# Power.net
KiCad netlist of a schematic drawn in Altium Designer
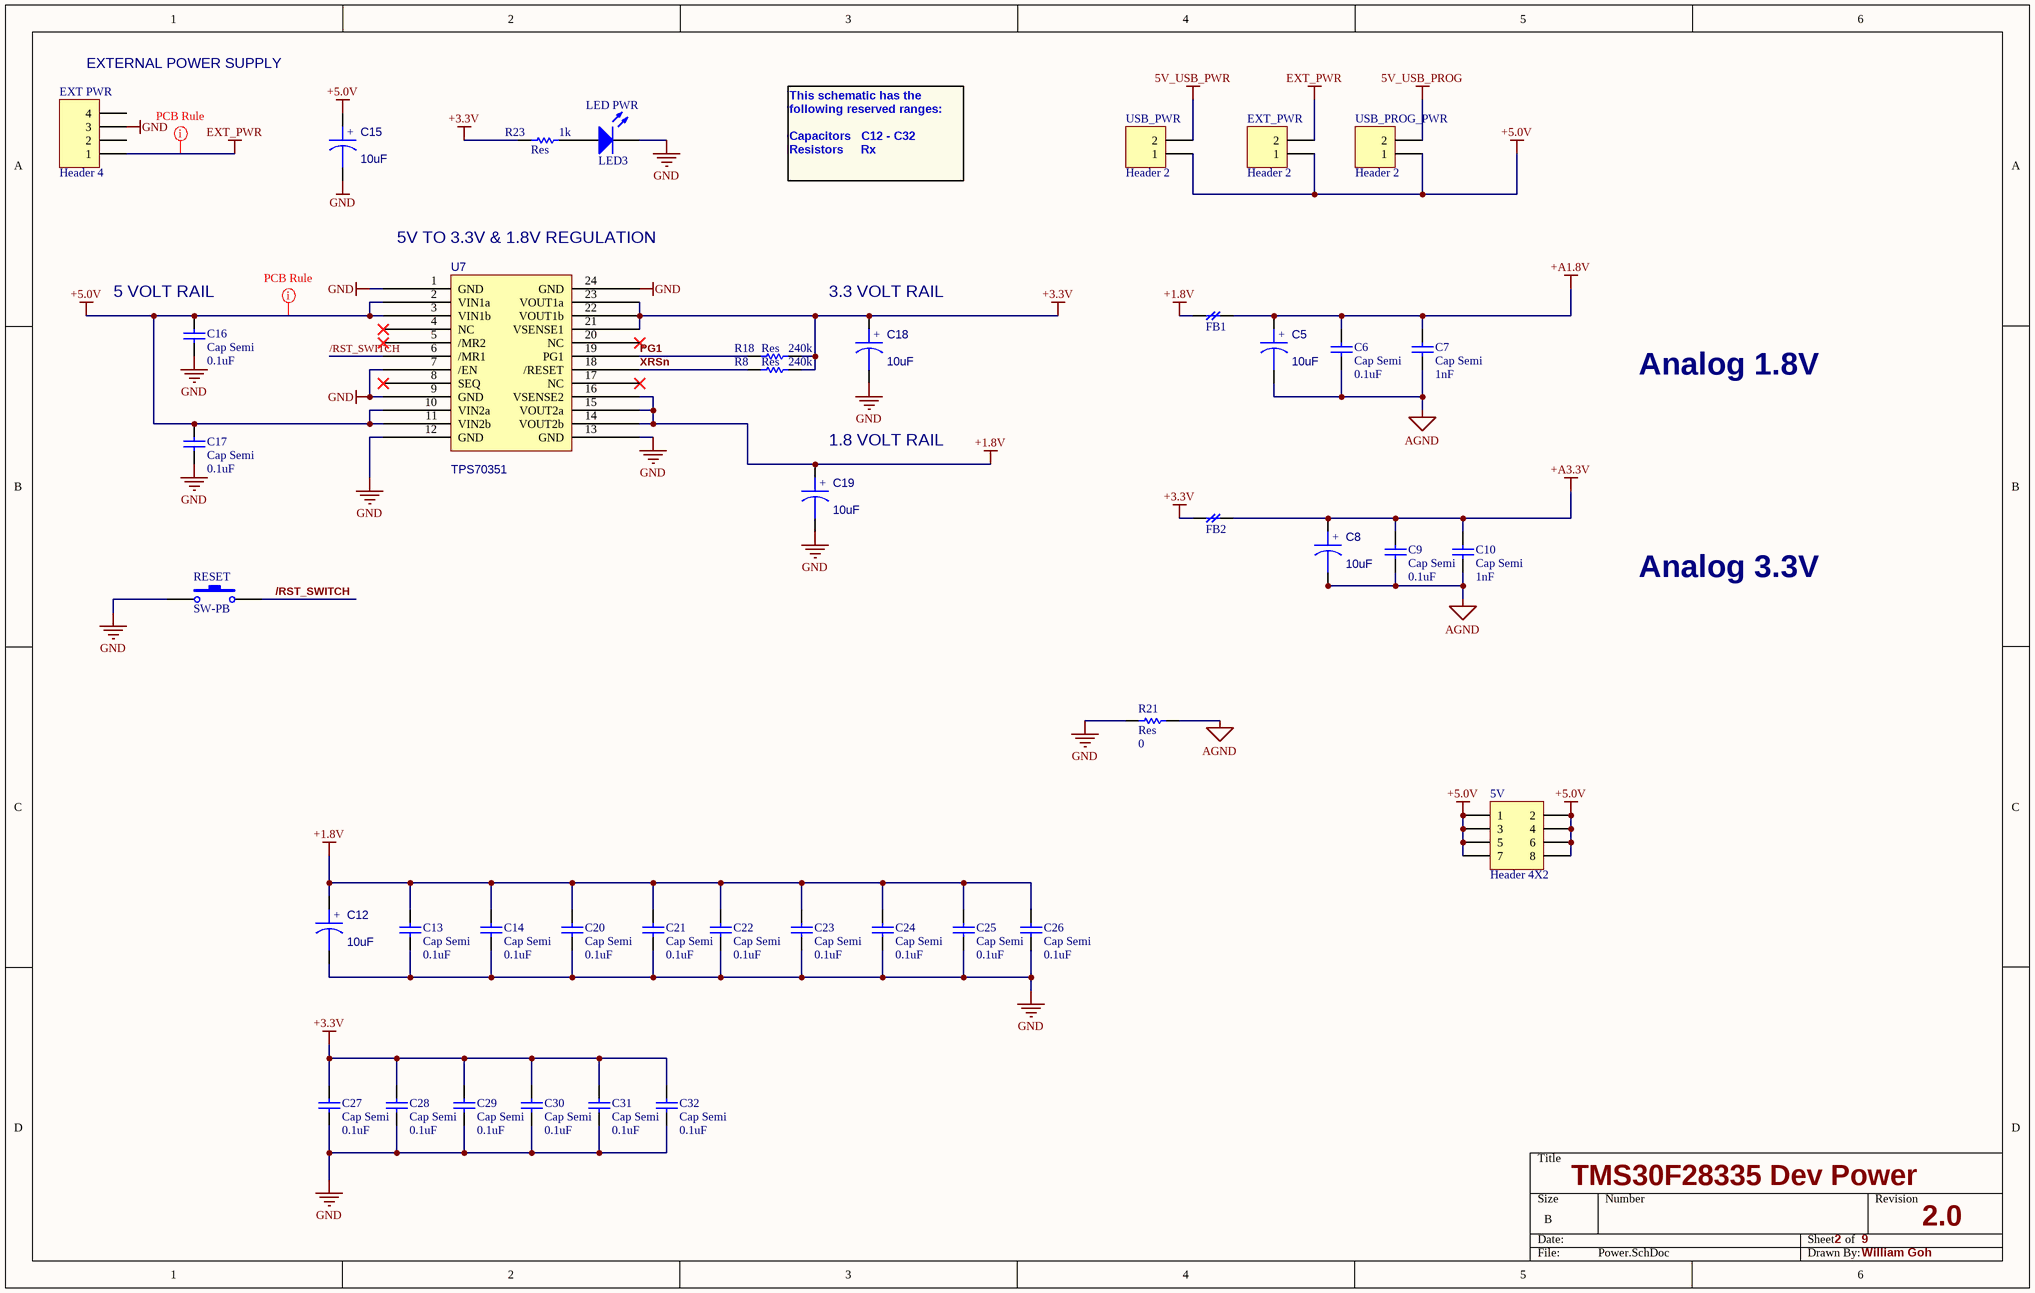
[diagram p0: Power.SchDoc]

(export (version "E")
  (design (tool "Eeschema 10.0.6"))
  (components
    (comp (ref "5V")
      (value "Header 4X2")
      (footprint "HDR2X4")
      (description "Header, 4-Pin, Dual row")
      (fields (field (name "PUBLISHER") "Altium Limited"))
      (libsource (lib "Miscellaneous Connectors") (part "Header 4X2"))
    )
    (comp (ref "C5")
      (value "10uF")
      (footprint "3528")
      (description "digi-399-3096-1-ND")
      (libsource (lib "*") (part "CAPACITOR POL"))
    )
    (comp (ref "C6")
      (value "Cap Semi")
      (footprint "0805")
      (description "Capacitor (Semiconductor SIM Model)")
      (fields (field (name "ALTIUM_VALUE") "0.1uF") (field (name "PUBLISHER") "Altium Limited"))
      (libsource (lib "Miscellaneous Devices") (part "Cap Semi"))
    )
    (comp (ref "C7")
      (value "Cap Semi")
      (footprint "0805")
      (description "Capacitor (Semiconductor SIM Model)")
      (fields (field (name "ALTIUM_VALUE") "1nF") (field (name "PUBLISHER") "Altium Limited"))
      (libsource (lib "Miscellaneous Devices") (part "Cap Semi"))
    )
    (comp (ref "C8")
      (value "10uF")
      (footprint "3528")
      (description "digi-399-3096-1-ND")
      (libsource (lib "*") (part "CAPACITOR POL"))
    )
    (comp (ref "C9")
      (value "Cap Semi")
      (footprint "0805")
      (description "Capacitor (Semiconductor SIM Model)")
      (fields (field (name "ALTIUM_VALUE") "0.1uF") (field (name "PUBLISHER") "Altium Limited"))
      (libsource (lib "Miscellaneous Devices") (part "Cap Semi"))
    )
    (comp (ref "C10")
      (value "Cap Semi")
      (footprint "0805")
      (description "Capacitor (Semiconductor SIM Model)")
      (fields (field (name "ALTIUM_VALUE") "1nF") (field (name "PUBLISHER") "Altium Limited"))
      (libsource (lib "Miscellaneous Devices") (part "Cap Semi"))
    )
    (comp (ref "C12")
      (value "10uF")
      (footprint "3528")
      (description "digi-399-1576-1-ND")
      (libsource (lib "*") (part "CAPACITOR POL"))
    )
    (comp (ref "C13")
      (value "Cap Semi")
      (footprint "0805")
      (description "Capacitor (Semiconductor SIM Model)")
      (fields (field (name "ALTIUM_VALUE") "0.1uF") (field (name "PUBLISHER") "Altium Limited"))
      (libsource (lib "Miscellaneous Devices") (part "Cap Semi"))
    )
    (comp (ref "C14")
      (value "Cap Semi")
      (footprint "0805")
      (description "Capacitor (Semiconductor SIM Model)")
      (fields (field (name "ALTIUM_VALUE") "0.1uF") (field (name "PUBLISHER") "Altium Limited"))
      (libsource (lib "Miscellaneous Devices") (part "Cap Semi"))
    )
    (comp (ref "C15")
      (value "10uF")
      (footprint "3528")
      (description "digi-399-1563-1-ND")
      (libsource (lib "*") (part "CAPACITOR POL"))
    )
    (comp (ref "C16")
      (value "Cap Semi")
      (footprint "0805")
      (description "Capacitor (Semiconductor SIM Model)")
      (fields (field (name "ALTIUM_VALUE") "0.1uF") (field (name "PUBLISHER") "Altium Limited"))
      (libsource (lib "Miscellaneous Devices") (part "Cap Semi"))
    )
    (comp (ref "C17")
      (value "Cap Semi")
      (footprint "0805")
      (description "Capacitor (Semiconductor SIM Model)")
      (fields (field (name "ALTIUM_VALUE") "0.1uF") (field (name "PUBLISHER") "Altium Limited"))
      (libsource (lib "Miscellaneous Devices") (part "Cap Semi"))
    )
    (comp (ref "C18")
      (value "10uF")
      (footprint "3528")
      (description "digi-399-3096-1-ND")
      (libsource (lib "*") (part "CAPACITOR POL"))
    )
    (comp (ref "C19")
      (value "10uF")
      (footprint "3528")
      (description "digi-399-1576-1-ND")
      (libsource (lib "*") (part "CAPACITOR POL"))
    )
    (comp (ref "C20")
      (value "Cap Semi")
      (footprint "0805")
      (description "Capacitor (Semiconductor SIM Model)")
      (fields (field (name "ALTIUM_VALUE") "0.1uF") (field (name "PUBLISHER") "Altium Limited"))
      (libsource (lib "Miscellaneous Devices") (part "Cap Semi"))
    )
    (comp (ref "C21")
      (value "Cap Semi")
      (footprint "0805")
      (description "Capacitor (Semiconductor SIM Model)")
      (fields (field (name "ALTIUM_VALUE") "0.1uF") (field (name "PUBLISHER") "Altium Limited"))
      (libsource (lib "Miscellaneous Devices") (part "Cap Semi"))
    )
    (comp (ref "C22")
      (value "Cap Semi")
      (footprint "0805")
      (description "Capacitor (Semiconductor SIM Model)")
      (fields (field (name "ALTIUM_VALUE") "0.1uF") (field (name "PUBLISHER") "Altium Limited"))
      (libsource (lib "Miscellaneous Devices") (part "Cap Semi"))
    )
    (comp (ref "C23")
      (value "Cap Semi")
      (footprint "0805")
      (description "Capacitor (Semiconductor SIM Model)")
      (fields (field (name "ALTIUM_VALUE") "0.1uF") (field (name "PUBLISHER") "Altium Limited"))
      (libsource (lib "Miscellaneous Devices") (part "Cap Semi"))
    )
    (comp (ref "C24")
      (value "Cap Semi")
      (footprint "0805")
      (description "Capacitor (Semiconductor SIM Model)")
      (fields (field (name "ALTIUM_VALUE") "0.1uF") (field (name "PUBLISHER") "Altium Limited"))
      (libsource (lib "Miscellaneous Devices") (part "Cap Semi"))
    )
    (comp (ref "C25")
      (value "Cap Semi")
      (footprint "0805")
      (description "Capacitor (Semiconductor SIM Model)")
      (fields (field (name "ALTIUM_VALUE") "0.1uF") (field (name "PUBLISHER") "Altium Limited"))
      (libsource (lib "Miscellaneous Devices") (part "Cap Semi"))
    )
    (comp (ref "C26")
      (value "Cap Semi")
      (footprint "0805")
      (description "Capacitor (Semiconductor SIM Model)")
      (fields (field (name "ALTIUM_VALUE") "0.1uF") (field (name "PUBLISHER") "Altium Limited"))
      (libsource (lib "Miscellaneous Devices") (part "Cap Semi"))
    )
    (comp (ref "C27")
      (value "Cap Semi")
      (footprint "0805")
      (description "Capacitor (Semiconductor SIM Model)")
      (fields (field (name "ALTIUM_VALUE") "0.1uF") (field (name "PUBLISHER") "Altium Limited"))
      (libsource (lib "Miscellaneous Devices") (part "Cap Semi"))
    )
    (comp (ref "C28")
      (value "Cap Semi")
      (footprint "0805")
      (description "Capacitor (Semiconductor SIM Model)")
      (fields (field (name "ALTIUM_VALUE") "0.1uF") (field (name "PUBLISHER") "Altium Limited"))
      (libsource (lib "Miscellaneous Devices") (part "Cap Semi"))
    )
    (comp (ref "C29")
      (value "Cap Semi")
      (footprint "0805")
      (description "Capacitor (Semiconductor SIM Model)")
      (fields (field (name "ALTIUM_VALUE") "0.1uF") (field (name "PUBLISHER") "Altium Limited"))
      (libsource (lib "Miscellaneous Devices") (part "Cap Semi"))
    )
    (comp (ref "C30")
      (value "Cap Semi")
      (footprint "0805")
      (description "Capacitor (Semiconductor SIM Model)")
      (fields (field (name "ALTIUM_VALUE") "0.1uF") (field (name "PUBLISHER") "Altium Limited"))
      (libsource (lib "Miscellaneous Devices") (part "Cap Semi"))
    )
    (comp (ref "C31")
      (value "Cap Semi")
      (footprint "0805")
      (description "Capacitor (Semiconductor SIM Model)")
      (fields (field (name "ALTIUM_VALUE") "0.1uF") (field (name "PUBLISHER") "Altium Limited"))
      (libsource (lib "Miscellaneous Devices") (part "Cap Semi"))
    )
    (comp (ref "C32")
      (value "Cap Semi")
      (footprint "0805")
      (description "Capacitor (Semiconductor SIM Model)")
      (fields (field (name "ALTIUM_VALUE") "0.1uF") (field (name "PUBLISHER") "Altium Limited"))
      (libsource (lib "Miscellaneous Devices") (part "Cap Semi"))
    )
    (comp (ref "EXT PWR")
      (value "Header 4")
      (footprint "HDR1X4")
      (description "Header, 4-Pin")
      (fields (field (name "PUBLISHER") "Altium Limited"))
      (libsource (lib "Miscellaneous Connectors") (part "Header 4"))
    )
    (comp (ref "EXT_PWR")
      (value "Header 2")
      (footprint "HDR1X2")
      (description "Header, 2-Pin")
      (fields (field (name "PUBLISHER") "Altium Limited"))
      (libsource (lib "Miscellaneous Connectors") (part "Header 2"))
    )
    (comp (ref "FB1")
      (value "Ferrite_Bead")
      (footprint "CR2012-0805")
      (description "Ferrite Bead")
      (libsource (lib "addl") (part "Ferrite_Bead"))
    )
    (comp (ref "FB2")
      (value "Ferrite_Bead")
      (footprint "CR2012-0805")
      (description "Ferrite Bead")
      (libsource (lib "addl") (part "Ferrite_Bead"))
    )
    (comp (ref "LED PWR")
      (value "LED3")
      (footprint "0805")
      (description "Typical BLUE SiC LED")
      (fields (field (name "PUBLISHER") "Altium Limited"))
      (libsource (lib "Miscellaneous Devices") (part "LED3"))
    )
    (comp (ref "R8")
      (value "Res")
      (footprint "0805")
      (description "Semiconductor Resistor")
      (fields (field (name "ALTIUM_VALUE") "240k") (field (name "PUBLISHER") "Altium Limited"))
      (libsource (lib "F28335_DSC_Breakout") (part "Res Semi"))
    )
    (comp (ref "R18")
      (value "Res")
      (footprint "0805")
      (description "Semiconductor Resistor")
      (fields (field (name "ALTIUM_VALUE") "240k") (field (name "PUBLISHER") "Altium Limited"))
      (libsource (lib "F28335_DSC_Breakout") (part "Res Semi"))
    )
    (comp (ref "R21")
      (value "Res")
      (footprint "0805")
      (description "Semiconductor Resistor")
      (fields (field (name "ALTIUM_VALUE") "0") (field (name "PUBLISHER") "Altium Limited"))
      (libsource (lib "F28335_DSC_Breakout") (part "Res Semi"))
    )
    (comp (ref "R23")
      (value "Res")
      (footprint "0805")
      (description "Semiconductor Resistor")
      (fields (field (name "ALTIUM_VALUE") "1k") (field (name "PUBLISHER") "Altium Limited"))
      (libsource (lib "F28335_DSC_Breakout") (part "Res Semi"))
    )
    (comp (ref "RESET")
      (value "SW-PB")
      (footprint "SWITCH_2PAD_SMD")
      (description "Switch")
      (fields (field (name "PUBLISHER") "Altium Limited"))
      (libsource (lib "Miscellaneous Devices") (part "SW-PB"))
    )
    (comp (ref "U7")
      (value "TPS70351")
      (footprint "PWP24")
      (description "IC 3.3V/1.8V LDO REG 24-HTSSOP")
      (libsource (lib "F28335_DSC_Breakout") (part "TPS70351"))
    )
    (comp (ref "USB_PROG_PWR")
      (value "Header 2")
      (footprint "HDR1X2")
      (description "Header, 2-Pin")
      (fields (field (name "PUBLISHER") "Altium Limited"))
      (libsource (lib "Miscellaneous Connectors") (part "Header 2"))
    )
    (comp (ref "USB_PWR")
      (value "Header 2")
      (footprint "HDR1X2")
      (description "Header, 2-Pin")
      (fields (field (name "PUBLISHER") "Altium Limited"))
      (libsource (lib "Miscellaneous Connectors") (part "Header 2"))
    )
  )
  (nets
    (net (code "1") (name "+1.8V") (class "Default")
      (node (ref "C12") (pin "1") (pinfunction "1_1") (pintype "passive"))
      (node (ref "C13") (pin "2") (pinfunction "2_2") (pintype "passive"))
      (node (ref "C14") (pin "2") (pinfunction "2_2") (pintype "passive"))
      (node (ref "C19") (pin "1") (pinfunction "1_1") (pintype "passive"))
      (node (ref "C20") (pin "2") (pinfunction "2_2") (pintype "passive"))
      (node (ref "C21") (pin "2") (pinfunction "2_2") (pintype "passive"))
      (node (ref "C22") (pin "2") (pinfunction "2_2") (pintype "passive"))
      (node (ref "C23") (pin "2") (pinfunction "2_2") (pintype "passive"))
      (node (ref "C24") (pin "2") (pinfunction "2_2") (pintype "passive"))
      (node (ref "C25") (pin "2") (pinfunction "2_2") (pintype "passive"))
      (node (ref "C26") (pin "2") (pinfunction "2_2") (pintype "passive"))
      (node (ref "FB1") (pin "1") (pinfunction "1_1") (pintype "passive"))
      (node (ref "U7") (pin "14") (pinfunction "VOUT2b_14") (pintype "passive"))
      (node (ref "U7") (pin "15") (pinfunction "VOUT2a_15") (pintype "passive"))
      (node (ref "U7") (pin "16") (pinfunction "VSENSE2_16") (pintype "passive"))
    )
    (net (code "2") (name "+3.3V") (class "Default")
      (node (ref "C18") (pin "1") (pinfunction "1_1") (pintype "passive"))
      (node (ref "C27") (pin "2") (pinfunction "2_2") (pintype "passive"))
      (node (ref "C28") (pin "2") (pinfunction "2_2") (pintype "passive"))
      (node (ref "C29") (pin "2") (pinfunction "2_2") (pintype "passive"))
      (node (ref "C30") (pin "2") (pinfunction "2_2") (pintype "passive"))
      (node (ref "C31") (pin "2") (pinfunction "2_2") (pintype "passive"))
      (node (ref "C32") (pin "2") (pinfunction "2_2") (pintype "passive"))
      (node (ref "FB2") (pin "1") (pinfunction "1_1") (pintype "passive"))
      (node (ref "R18") (pin "2") (pinfunction "2_2") (pintype "passive"))
      (node (ref "R23") (pin "1") (pinfunction "1_1") (pintype "passive"))
      (node (ref "R8") (pin "2") (pinfunction "2_2") (pintype "passive"))
      (node (ref "U7") (pin "21") (pinfunction "VSENSE1_21") (pintype "passive"))
      (node (ref "U7") (pin "22") (pinfunction "VOUT1b_22") (pintype "passive"))
      (node (ref "U7") (pin "23") (pinfunction "VOUT1a_23") (pintype "passive"))
    )
    (net (code "3") (name "+5.0V") (class "Default")
      (node (ref "5V") (pin "1") (pinfunction "1_1") (pintype "passive"))
      (node (ref "5V") (pin "2") (pinfunction "2_2") (pintype "passive"))
      (node (ref "5V") (pin "3") (pinfunction "3_3") (pintype "passive"))
      (node (ref "5V") (pin "4") (pinfunction "4_4") (pintype "passive"))
      (node (ref "5V") (pin "5") (pinfunction "5_5") (pintype "passive"))
      (node (ref "5V") (pin "6") (pinfunction "6_6") (pintype "passive"))
      (node (ref "5V") (pin "7") (pinfunction "7_7") (pintype "passive"))
      (node (ref "5V") (pin "8") (pinfunction "8_8") (pintype "passive"))
      (node (ref "C15") (pin "1") (pinfunction "1_1") (pintype "passive"))
      (node (ref "C16") (pin "2") (pinfunction "2_2") (pintype "passive"))
      (node (ref "C17") (pin "2") (pinfunction "2_2") (pintype "passive"))
      (node (ref "EXT_PWR") (pin "1") (pinfunction "1_1") (pintype "passive"))
      (node (ref "U7") (pin "10") (pinfunction "VIN2a_10") (pintype "passive"))
      (node (ref "U7") (pin "11") (pinfunction "VIN2b_11") (pintype "passive"))
      (node (ref "U7") (pin "2") (pinfunction "VIN1a_2") (pintype "passive"))
      (node (ref "U7") (pin "3") (pinfunction "VIN1b_3") (pintype "passive"))
      (node (ref "USB_PROG_PWR") (pin "1") (pinfunction "1_1") (pintype "passive"))
      (node (ref "USB_PWR") (pin "1") (pinfunction "1_1") (pintype "passive"))
    )
    (net (code "4") (name "+A1.8V") (class "Default")
      (node (ref "C5") (pin "1") (pinfunction "1_1") (pintype "passive"))
      (node (ref "C6") (pin "2") (pinfunction "2_2") (pintype "passive"))
      (node (ref "C7") (pin "2") (pinfunction "2_2") (pintype "passive"))
      (node (ref "FB1") (pin "2") (pinfunction "2_2") (pintype "passive"))
    )
    (net (code "5") (name "+A3.3V") (class "Default")
      (node (ref "C10") (pin "2") (pinfunction "2_2") (pintype "passive"))
      (node (ref "C8") (pin "1") (pinfunction "1_1") (pintype "passive"))
      (node (ref "C9") (pin "2") (pinfunction "2_2") (pintype "passive"))
      (node (ref "FB2") (pin "2") (pinfunction "2_2") (pintype "passive"))
    )
    (net (code "6") (name "/PG1") (class "Default")
      (node (ref "R18") (pin "1") (pinfunction "1_1") (pintype "passive"))
      (node (ref "U7") (pin "19") (pinfunction "PG1_19") (pintype "passive"))
    )
    (net (code "7") (name "/XRSn") (class "Default")
      (node (ref "R8") (pin "1") (pinfunction "1_1") (pintype "passive"))
      (node (ref "U7") (pin "18") (pinfunction "/RESET_18") (pintype "passive"))
    )
    (net (code "8") (name "/{slash}RST_SWITCH") (class "Default")
      (node (ref "RESET") (pin "2") (pinfunction "2_2") (pintype "passive"))
      (node (ref "U7") (pin "6") (pinfunction "/MR1_6") (pintype "passive"))
    )
    (net (code "9") (name "5V_USB_PROG") (class "Default")
      (node (ref "USB_PROG_PWR") (pin "2") (pinfunction "2_2") (pintype "passive"))
    )
    (net (code "10") (name "5V_USB_PWR") (class "Default")
      (node (ref "USB_PWR") (pin "2") (pinfunction "2_2") (pintype "passive"))
    )
    (net (code "11") (name "AGND") (class "Default")
      (node (ref "C10") (pin "1") (pinfunction "1_1") (pintype "passive"))
      (node (ref "C5") (pin "2") (pinfunction "2_2") (pintype "passive"))
      (node (ref "C6") (pin "1") (pinfunction "1_1") (pintype "passive"))
      (node (ref "C7") (pin "1") (pinfunction "1_1") (pintype "passive"))
      (node (ref "C8") (pin "2") (pinfunction "2_2") (pintype "passive"))
      (node (ref "C9") (pin "1") (pinfunction "1_1") (pintype "passive"))
      (node (ref "R21") (pin "2") (pinfunction "2_2") (pintype "passive"))
    )
    (net (code "12") (name "EXT_PWR") (class "Default")
      (node (ref "EXT PWR") (pin "1") (pinfunction "1_1") (pintype "passive"))
      (node (ref "EXT_PWR") (pin "2") (pinfunction "2_2") (pintype "passive"))
    )
    (net (code "13") (name "GND") (class "Default")
      (node (ref "C12") (pin "2") (pinfunction "2_2") (pintype "passive"))
      (node (ref "C13") (pin "1") (pinfunction "1_1") (pintype "passive"))
      (node (ref "C14") (pin "1") (pinfunction "1_1") (pintype "passive"))
      (node (ref "C15") (pin "2") (pinfunction "2_2") (pintype "passive"))
      (node (ref "C16") (pin "1") (pinfunction "1_1") (pintype "passive"))
      (node (ref "C17") (pin "1") (pinfunction "1_1") (pintype "passive"))
      (node (ref "C18") (pin "2") (pinfunction "2_2") (pintype "passive"))
      (node (ref "C19") (pin "2") (pinfunction "2_2") (pintype "passive"))
      (node (ref "C20") (pin "1") (pinfunction "1_1") (pintype "passive"))
      (node (ref "C21") (pin "1") (pinfunction "1_1") (pintype "passive"))
      (node (ref "C22") (pin "1") (pinfunction "1_1") (pintype "passive"))
      (node (ref "C23") (pin "1") (pinfunction "1_1") (pintype "passive"))
      (node (ref "C24") (pin "1") (pinfunction "1_1") (pintype "passive"))
      (node (ref "C25") (pin "1") (pinfunction "1_1") (pintype "passive"))
      (node (ref "C26") (pin "1") (pinfunction "1_1") (pintype "passive"))
      (node (ref "C27") (pin "1") (pinfunction "1_1") (pintype "passive"))
      (node (ref "C28") (pin "1") (pinfunction "1_1") (pintype "passive"))
      (node (ref "C29") (pin "1") (pinfunction "1_1") (pintype "passive"))
      (node (ref "C30") (pin "1") (pinfunction "1_1") (pintype "passive"))
      (node (ref "C31") (pin "1") (pinfunction "1_1") (pintype "passive"))
      (node (ref "C32") (pin "1") (pinfunction "1_1") (pintype "passive"))
      (node (ref "EXT PWR") (pin "3") (pinfunction "3_3") (pintype "passive"))
      (node (ref "LED PWR") (pin "2") (pinfunction "K_2") (pintype "passive"))
      (node (ref "R21") (pin "1") (pinfunction "1_1") (pintype "passive"))
      (node (ref "RESET") (pin "1") (pinfunction "1_1") (pintype "passive"))
      (node (ref "U7") (pin "1") (pinfunction "GND_1") (pintype "passive"))
      (node (ref "U7") (pin "12") (pinfunction "GND_12") (pintype "passive"))
      (node (ref "U7") (pin "13") (pinfunction "GND_13") (pintype "passive"))
      (node (ref "U7") (pin "24") (pinfunction "GND_24") (pintype "passive"))
      (node (ref "U7") (pin "7") (pinfunction "/EN_7") (pintype "passive"))
      (node (ref "U7") (pin "9") (pinfunction "GND_9") (pintype "passive"))
    )
    (net (code "14") (name "Net-(LED PWR-A)") (class "Default")
      (node (ref "LED PWR") (pin "1") (pinfunction "A_1") (pintype "passive"))
      (node (ref "R23") (pin "2") (pinfunction "2_2") (pintype "passive"))
    )
    (net (code "15") (name "unconnected-(EXT PWR-Pad2)") (class "Default")
      (node (ref "EXT PWR") (pin "2") (pinfunction "2_2") (pintype "passive"))
    )
    (net (code "16") (name "unconnected-(EXT PWR-Pad4)") (class "Default")
      (node (ref "EXT PWR") (pin "4") (pinfunction "4_4") (pintype "passive"))
    )
    (net (code "17") (name "unconnected-(U7-NC-Pad4)") (class "Default")
      (node (ref "U7") (pin "4") (pinfunction "NC_4") (pintype "passive+no_connect"))
    )
    (net (code "18") (name "unconnected-(U7-NC-Pad17)") (class "Default")
      (node (ref "U7") (pin "17") (pinfunction "NC_17") (pintype "passive+no_connect"))
    )
    (net (code "19") (name "unconnected-(U7-NC-Pad20)") (class "Default")
      (node (ref "U7") (pin "20") (pinfunction "NC_20") (pintype "passive+no_connect"))
    )
    (net (code "20") (name "unconnected-(U7-SEQ-Pad8)") (class "Default")
      (node (ref "U7") (pin "8") (pinfunction "SEQ_8") (pintype "passive+no_connect"))
    )
    (net (code "21") (name "unconnected-(U7-{slash}MR2-Pad5)") (class "Default")
      (node (ref "U7") (pin "5") (pinfunction "/MR2_5") (pintype "passive+no_connect"))
    )
  )
)
